# Nusbio_Test_GPIOS_Extension.net
KiCad netlist of a schematic drawn in EAGLE
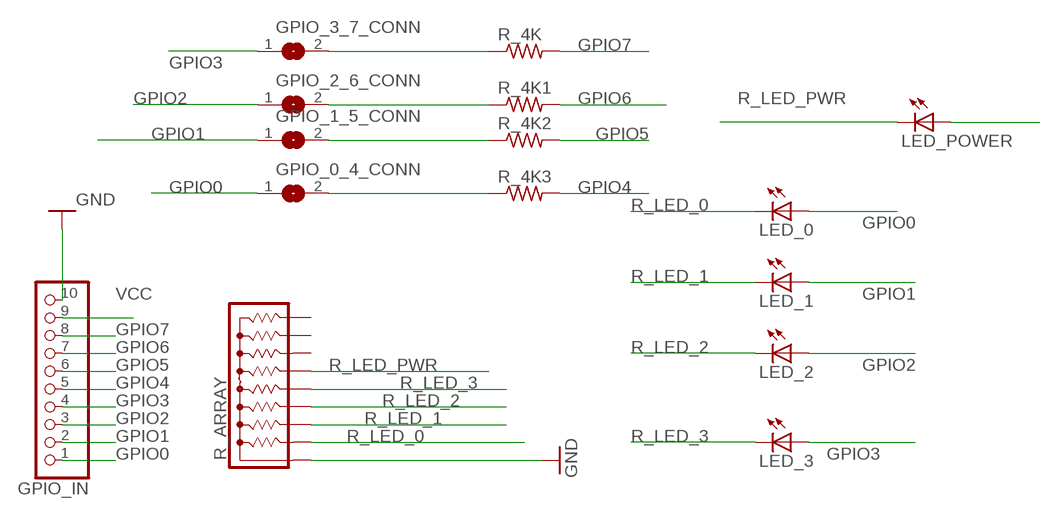
[diagram p0: schematic, sheet 1]

(export (version "E")
  (design (tool "Eeschema 10.0.6"))
  (components
    (comp (ref "GPIO_0_4_CONN")
      (value "SOLDERJUMPERREFLOW")
      (footprint "eagle-import:SOLDERJUMPER_REFLOW")
      (libsource (lib "eagle-import") (part "SOLDERJUMPERREFLOW"))
    )
    (comp (ref "GPIO_1_5_CONN")
      (value "SOLDERJUMPERREFLOW")
      (footprint "eagle-import:SOLDERJUMPER_REFLOW")
      (libsource (lib "eagle-import") (part "SOLDERJUMPERREFLOW"))
    )
    (comp (ref "GPIO_2_6_CONN")
      (value "SOLDERJUMPERREFLOW")
      (footprint "eagle-import:SOLDERJUMPER_REFLOW")
      (libsource (lib "eagle-import") (part "SOLDERJUMPERREFLOW"))
    )
    (comp (ref "GPIO_3_7_CONN")
      (value "SOLDERJUMPERREFLOW")
      (footprint "eagle-import:SOLDERJUMPER_REFLOW")
      (libsource (lib "eagle-import") (part "SOLDERJUMPERREFLOW"))
    )
    (comp (ref "GPIO_IN")
      (value "PINHD-1X10")
      (footprint "eagle-import:1X10-BIG")
      (libsource (lib "eagle-import") (part "PINHD-1X10"))
    )
    (comp (ref "LED_0")
      (value "LEDSMT1206")
      (footprint "eagle-import:1206")
      (libsource (lib "eagle-import") (part "LEDSMT1206"))
    )
    (comp (ref "LED_1")
      (value "LEDSMT1206")
      (footprint "eagle-import:1206")
      (libsource (lib "eagle-import") (part "LEDSMT1206"))
    )
    (comp (ref "LED_2")
      (value "LEDSMT1206")
      (footprint "eagle-import:1206")
      (libsource (lib "eagle-import") (part "LEDSMT1206"))
    )
    (comp (ref "LED_3")
      (value "LEDSMT1206")
      (footprint "eagle-import:1206")
      (libsource (lib "eagle-import") (part "LEDSMT1206"))
    )
    (comp (ref "LED_POWER")
      (value "LEDSMT1206")
      (footprint "eagle-import:1206")
      (libsource (lib "eagle-import") (part "LEDSMT1206"))
    )
    (comp (ref "R_4K")
      (value "R-US_R1206")
      (footprint "eagle-import:R1206")
      (libsource (lib "eagle-import") (part "R-US_R1206"))
    )
    (comp (ref "R_4K1")
      (value "R-US_R1206")
      (footprint "eagle-import:R1206")
      (libsource (lib "eagle-import") (part "R-US_R1206"))
    )
    (comp (ref "R_4K2")
      (value "R-US_R1206")
      (footprint "eagle-import:R1206")
      (libsource (lib "eagle-import") (part "R-US_R1206"))
    )
    (comp (ref "R_4K3")
      (value "R-US_R1206")
      (footprint "eagle-import:R1206")
      (libsource (lib "eagle-import") (part "R-US_R1206"))
    )
    (comp (ref "R_ARRAY")
      (value "4609X")
      (footprint "eagle-import:SIP9")
      (libsource (lib "eagle-import") (part "4609X"))
    )
  )
  (nets
    (net (code "1") (name "/GPIO0") (class "Default")
      (node (ref "GPIO_0_4_CONN") (pin "1") (pinfunction "1_1") (pintype "passive"))
      (node (ref "GPIO_IN") (pin "1") (pinfunction "1_1") (pintype "passive"))
      (node (ref "LED_0") (pin "A") (pinfunction "A_A") (pintype "passive"))
    )
    (net (code "2") (name "/GPIO1") (class "Default")
      (node (ref "GPIO_1_5_CONN") (pin "1") (pinfunction "1_1") (pintype "passive"))
      (node (ref "GPIO_IN") (pin "2") (pinfunction "2_2") (pintype "passive"))
      (node (ref "LED_1") (pin "A") (pinfunction "A_A") (pintype "passive"))
    )
    (net (code "3") (name "/GPIO2") (class "Default")
      (node (ref "GPIO_2_6_CONN") (pin "1") (pinfunction "1_1") (pintype "passive"))
      (node (ref "GPIO_IN") (pin "3") (pinfunction "3_3") (pintype "passive"))
      (node (ref "LED_2") (pin "A") (pinfunction "A_A") (pintype "passive"))
    )
    (net (code "4") (name "/GPIO3") (class "Default")
      (node (ref "GPIO_3_7_CONN") (pin "1") (pinfunction "1_1") (pintype "passive"))
      (node (ref "GPIO_IN") (pin "4") (pinfunction "4_4") (pintype "passive"))
      (node (ref "LED_3") (pin "A") (pinfunction "A_A") (pintype "passive"))
    )
    (net (code "5") (name "/GPIO4") (class "Default")
      (node (ref "GPIO_IN") (pin "5") (pinfunction "5_5") (pintype "passive"))
      (node (ref "R_4K3") (pin "2") (pinfunction "2_2") (pintype "passive"))
    )
    (net (code "6") (name "/GPIO5") (class "Default")
      (node (ref "GPIO_IN") (pin "6") (pinfunction "6_6") (pintype "passive"))
      (node (ref "R_4K2") (pin "2") (pinfunction "2_2") (pintype "passive"))
    )
    (net (code "7") (name "/GPIO6") (class "Default")
      (node (ref "GPIO_IN") (pin "7") (pinfunction "7_7") (pintype "passive"))
      (node (ref "R_4K1") (pin "2") (pinfunction "2_2") (pintype "passive"))
    )
    (net (code "8") (name "/GPIO7") (class "Default")
      (node (ref "GPIO_IN") (pin "8") (pinfunction "8_8") (pintype "passive"))
      (node (ref "R_4K") (pin "2") (pinfunction "2_2") (pintype "passive"))
    )
    (net (code "9") (name "/R_LED_0") (class "Default")
      (node (ref "LED_0") (pin "C") (pinfunction "C_C") (pintype "passive"))
      (node (ref "R_ARRAY") (pin "2") (pinfunction "2_2") (pintype "passive"))
    )
    (net (code "10") (name "/R_LED_1") (class "Default")
      (node (ref "LED_1") (pin "C") (pinfunction "C_C") (pintype "passive"))
      (node (ref "R_ARRAY") (pin "3") (pinfunction "3_3") (pintype "passive"))
    )
    (net (code "11") (name "/R_LED_2") (class "Default")
      (node (ref "LED_2") (pin "C") (pinfunction "C_C") (pintype "passive"))
      (node (ref "R_ARRAY") (pin "4") (pinfunction "4_4") (pintype "passive"))
    )
    (net (code "12") (name "/R_LED_3") (class "Default")
      (node (ref "LED_3") (pin "C") (pinfunction "C_C") (pintype "passive"))
      (node (ref "R_ARRAY") (pin "5") (pinfunction "5_5") (pintype "passive"))
    )
    (net (code "13") (name "/R_LED_PWR") (class "Default")
      (node (ref "LED_POWER") (pin "C") (pinfunction "C_C") (pintype "passive"))
      (node (ref "R_ARRAY") (pin "6") (pinfunction "6_6") (pintype "passive"))
    )
    (net (code "14") (name "/VCC") (class "Default")
      (node (ref "GPIO_IN") (pin "9") (pinfunction "9_9") (pintype "passive"))
      (node (ref "LED_POWER") (pin "A") (pinfunction "A_A") (pintype "passive"))
    )
    (net (code "15") (name "GND") (class "Default")
      (node (ref "GPIO_IN") (pin "10") (pinfunction "10_10") (pintype "passive"))
      (node (ref "R_ARRAY") (pin "1") (pinfunction "1_1") (pintype "passive"))
    )
    (net (code "16") (name "Net-(GPIO_0_4_CONN-Pad2)") (class "Default")
      (node (ref "GPIO_0_4_CONN") (pin "2") (pinfunction "2_2") (pintype "passive"))
      (node (ref "R_4K3") (pin "1") (pinfunction "1_1") (pintype "passive"))
    )
    (net (code "17") (name "Net-(GPIO_1_5_CONN-Pad2)") (class "Default")
      (node (ref "GPIO_1_5_CONN") (pin "2") (pinfunction "2_2") (pintype "passive"))
      (node (ref "R_4K2") (pin "1") (pinfunction "1_1") (pintype "passive"))
    )
    (net (code "18") (name "Net-(GPIO_2_6_CONN-Pad2)") (class "Default")
      (node (ref "GPIO_2_6_CONN") (pin "2") (pinfunction "2_2") (pintype "passive"))
      (node (ref "R_4K1") (pin "1") (pinfunction "1_1") (pintype "passive"))
    )
    (net (code "19") (name "Net-(GPIO_3_7_CONN-Pad2)") (class "Default")
      (node (ref "GPIO_3_7_CONN") (pin "2") (pinfunction "2_2") (pintype "passive"))
      (node (ref "R_4K") (pin "1") (pinfunction "1_1") (pintype "passive"))
    )
    (net (code "20") (name "unconnected-(R_ARRAY-Pad7)") (class "Default")
      (node (ref "R_ARRAY") (pin "7") (pinfunction "7_7") (pintype "passive"))
    )
    (net (code "21") (name "unconnected-(R_ARRAY-Pad8)") (class "Default")
      (node (ref "R_ARRAY") (pin "8") (pinfunction "8_8") (pintype "passive"))
    )
    (net (code "22") (name "unconnected-(R_ARRAY-Pad9)") (class "Default")
      (node (ref "R_ARRAY") (pin "9") (pinfunction "9_9") (pintype "passive"))
    )
  )
)
